# drivessop.net
KiCad netlist of a schematic drawn in EAGLE
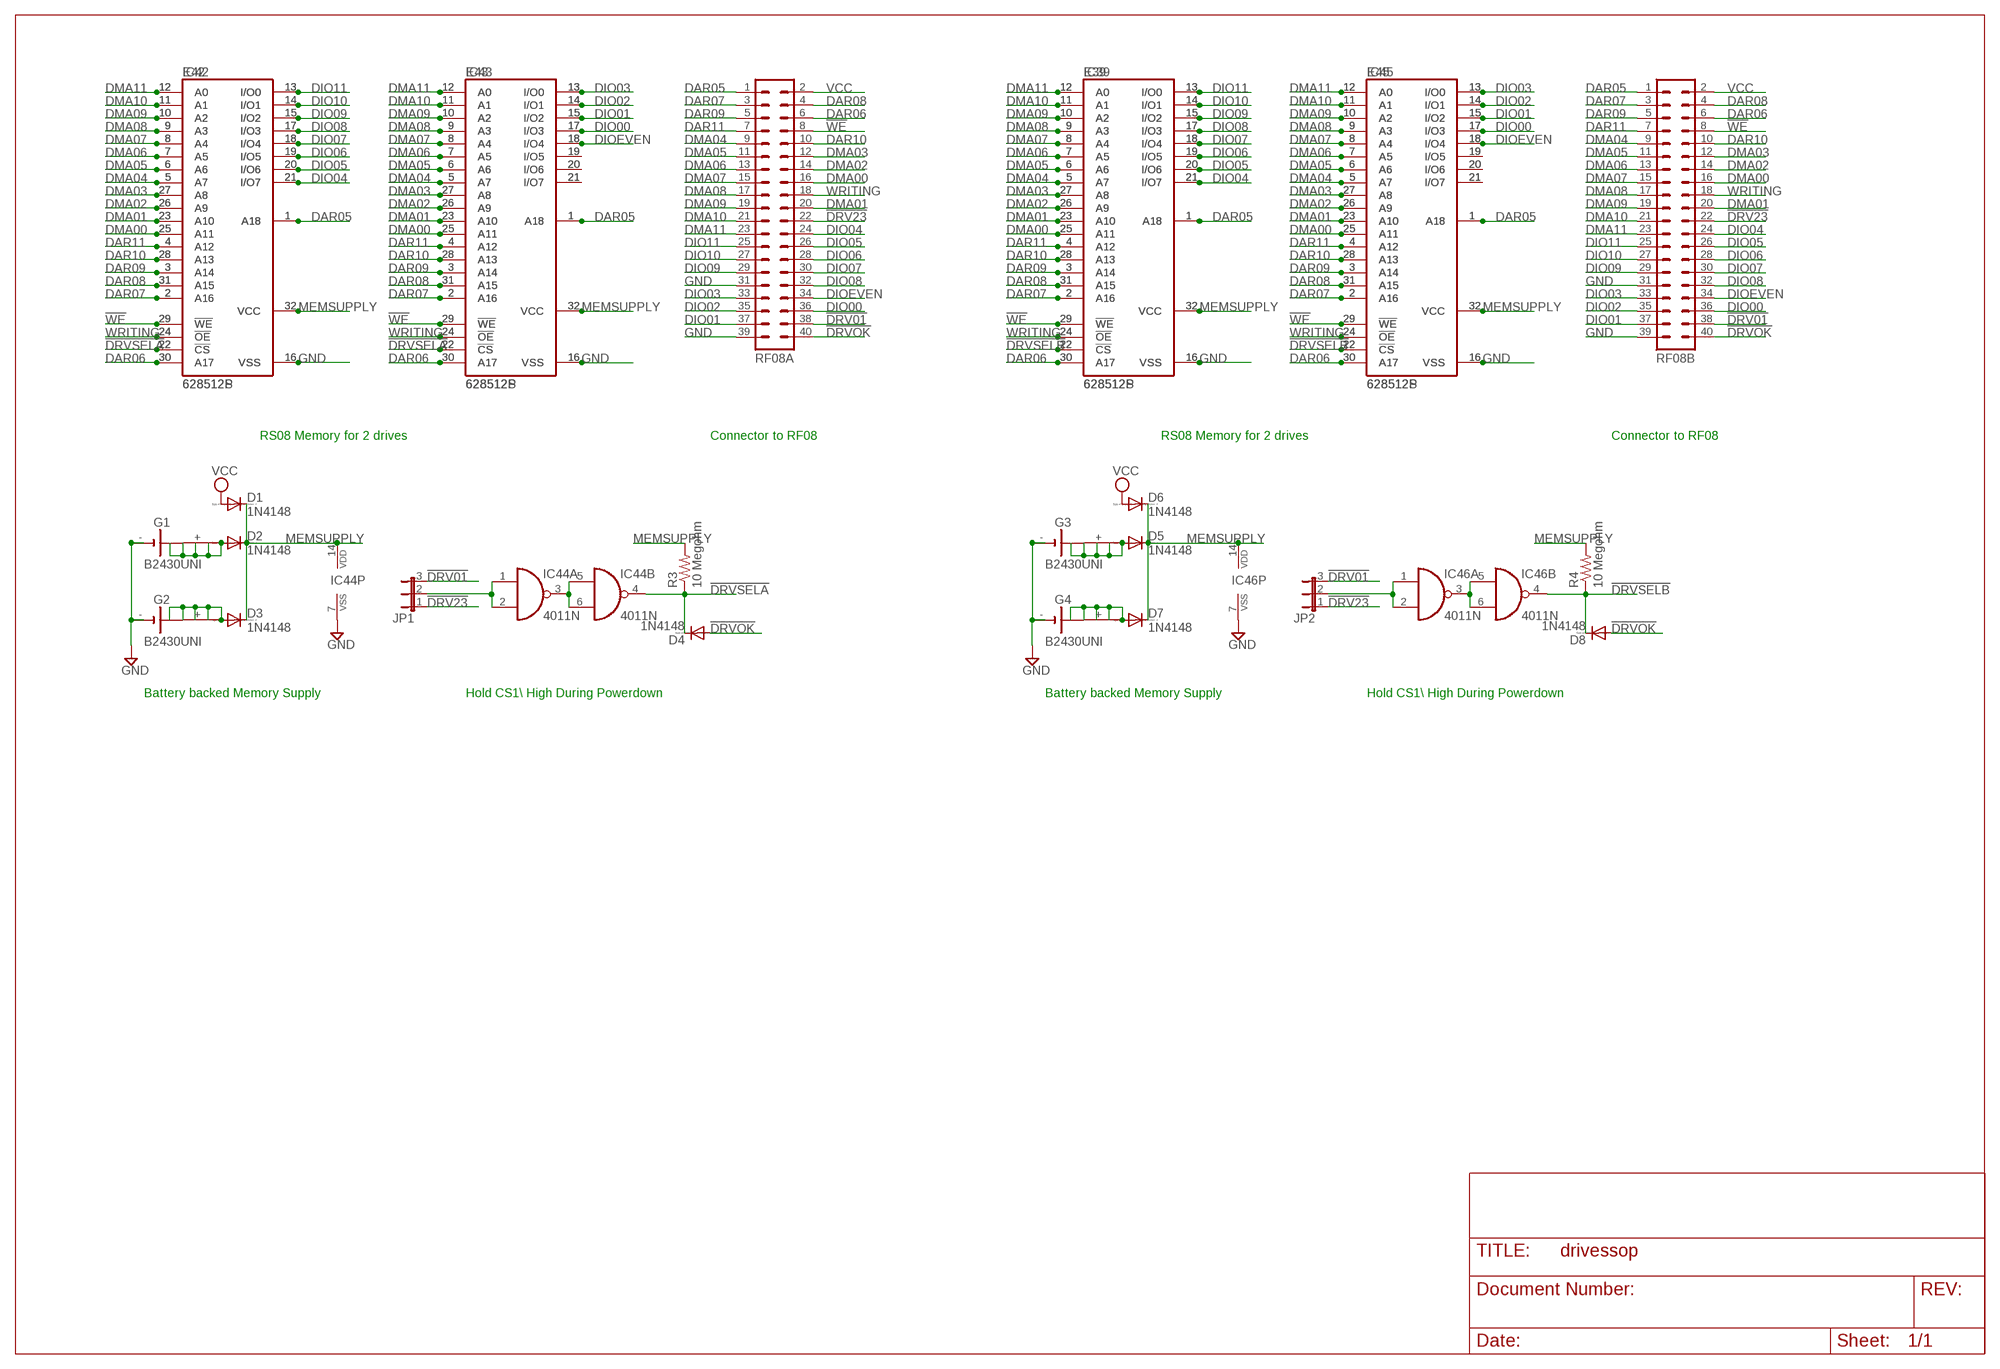
[diagram p0: schematic, sheet 1]

(export (version "E")
  (design (tool "Eeschema 10.0.6"))
  (components
    (comp (ref "D1")
      (value "1N4148")
      (footprint "eagle-import:DO35-10")
      (libsource (lib "eagle-import") (part "1N4148DO35-10"))
    )
    (comp (ref "D2")
      (value "1N4148")
      (footprint "eagle-import:DO35-10")
      (libsource (lib "eagle-import") (part "1N4148DO35-10"))
    )
    (comp (ref "D3")
      (value "1N4148")
      (footprint "eagle-import:DO35-10")
      (libsource (lib "eagle-import") (part "1N4148DO35-10"))
    )
    (comp (ref "D4")
      (value "1N4148")
      (footprint "eagle-import:DO35-10")
      (libsource (lib "eagle-import") (part "1N4148DO35-10"))
    )
    (comp (ref "D5")
      (value "1N4148")
      (footprint "eagle-import:DO35-10")
      (libsource (lib "eagle-import") (part "1N4148DO35-10"))
    )
    (comp (ref "D6")
      (value "1N4148")
      (footprint "eagle-import:DO35-10")
      (libsource (lib "eagle-import") (part "1N4148DO35-10"))
    )
    (comp (ref "D7")
      (value "1N4148")
      (footprint "eagle-import:DO35-10")
      (libsource (lib "eagle-import") (part "1N4148DO35-10"))
    )
    (comp (ref "D8")
      (value "1N4148")
      (footprint "eagle-import:DO35-10")
      (libsource (lib "eagle-import") (part "1N4148DO35-10"))
    )
    (comp (ref "E39")
      (value "628512S")
      (footprint "eagle-import:S032L")
      (libsource (lib "eagle-import") (part "628512S"))
    )
    (comp (ref "E42")
      (value "628512S")
      (footprint "eagle-import:S032L")
      (libsource (lib "eagle-import") (part "628512S"))
    )
    (comp (ref "E43")
      (value "628512S")
      (footprint "eagle-import:S032L")
      (libsource (lib "eagle-import") (part "628512S"))
    )
    (comp (ref "E45")
      (value "628512S")
      (footprint "eagle-import:S032L")
      (libsource (lib "eagle-import") (part "628512S"))
    )
    (comp (ref "G1")
      (value "B2430UNI")
      (footprint "eagle-import:B2430UNI")
      (libsource (lib "eagle-import") (part "B2430UNI"))
    )
    (comp (ref "G2")
      (value "B2430UNI")
      (footprint "eagle-import:B2430UNI")
      (libsource (lib "eagle-import") (part "B2430UNI"))
    )
    (comp (ref "G3")
      (value "B2430UNI")
      (footprint "eagle-import:B2430UNI")
      (libsource (lib "eagle-import") (part "B2430UNI"))
    )
    (comp (ref "G4")
      (value "B2430UNI")
      (footprint "eagle-import:B2430UNI")
      (libsource (lib "eagle-import") (part "B2430UNI"))
    )
    (comp (ref "IC39")
      (value "628512P")
      (footprint "eagle-import:DIL32")
      (libsource (lib "eagle-import") (part "628512P"))
    )
    (comp (ref "IC42")
      (value "628512P")
      (footprint "eagle-import:DIL32")
      (libsource (lib "eagle-import") (part "628512P"))
    )
    (comp (ref "IC43")
      (value "628512P")
      (footprint "eagle-import:DIL32")
      (libsource (lib "eagle-import") (part "628512P"))
    )
    (comp (ref "IC44")
      (value "4011N")
      (footprint "eagle-import:DIL14")
      (libsource (lib "eagle-import") (part "4011N"))
    )
    (comp (ref "IC45")
      (value "628512P")
      (footprint "eagle-import:DIL32")
      (libsource (lib "eagle-import") (part "628512P"))
    )
    (comp (ref "IC46")
      (value "4011N")
      (footprint "eagle-import:DIL14")
      (libsource (lib "eagle-import") (part "4011N"))
    )
    (comp (ref "JP1")
      (value "JP2E")
      (footprint "eagle-import:JP2")
      (libsource (lib "eagle-import") (part "JP2E"))
    )
    (comp (ref "JP2")
      (value "JP2E")
      (footprint "eagle-import:JP2")
      (libsource (lib "eagle-import") (part "JP2E"))
    )
    (comp (ref "R3")
      (value "10 Megohm")
      (footprint "eagle-import:0207_10")
      (libsource (lib "eagle-import") (part "R-US_0207/10"))
    )
    (comp (ref "R4")
      (value "10 Megohm")
      (footprint "eagle-import:0207_10")
      (libsource (lib "eagle-import") (part "R-US_0207/10"))
    )
    (comp (ref "RF08A")
      (value "MA20-2")
      (footprint "eagle-import:MA20-2")
      (libsource (lib "eagle-import") (part "MA20-2"))
    )
    (comp (ref "RF08B")
      (value "MA20-2")
      (footprint "eagle-import:MA20-2")
      (libsource (lib "eagle-import") (part "MA20-2"))
    )
  )
  (nets
    (net (code "1") (name "/DAR05") (class "Default")
      (node (ref "E39") (pin "1") (pinfunction "A18_1") (pintype "input"))
      (node (ref "E42") (pin "1") (pinfunction "A18_1") (pintype "input"))
      (node (ref "E43") (pin "1") (pinfunction "A18_1") (pintype "input"))
      (node (ref "E45") (pin "1") (pinfunction "A18_1") (pintype "input"))
      (node (ref "IC39") (pin "1") (pinfunction "A18_1") (pintype "input"))
      (node (ref "IC42") (pin "1") (pinfunction "A18_1") (pintype "input"))
      (node (ref "IC43") (pin "1") (pinfunction "A18_1") (pintype "input"))
      (node (ref "IC45") (pin "1") (pinfunction "A18_1") (pintype "input"))
      (node (ref "RF08A") (pin "1") (pinfunction "1_1") (pintype "passive"))
      (node (ref "RF08B") (pin "1") (pinfunction "1_1") (pintype "passive"))
    )
    (net (code "2") (name "/DAR06") (class "Default")
      (node (ref "E39") (pin "30") (pinfunction "A17_30") (pintype "input"))
      (node (ref "E42") (pin "30") (pinfunction "A17_30") (pintype "input"))
      (node (ref "E43") (pin "30") (pinfunction "A17_30") (pintype "input"))
      (node (ref "E45") (pin "30") (pinfunction "A17_30") (pintype "input"))
      (node (ref "IC39") (pin "30") (pinfunction "A17_30") (pintype "input"))
      (node (ref "IC42") (pin "30") (pinfunction "A17_30") (pintype "input"))
      (node (ref "IC43") (pin "30") (pinfunction "A17_30") (pintype "input"))
      (node (ref "IC45") (pin "30") (pinfunction "A17_30") (pintype "input"))
      (node (ref "RF08A") (pin "6") (pinfunction "6_6") (pintype "passive"))
      (node (ref "RF08B") (pin "6") (pinfunction "6_6") (pintype "passive"))
    )
    (net (code "3") (name "/DAR07") (class "Default")
      (node (ref "E39") (pin "2") (pinfunction "A16_2") (pintype "input"))
      (node (ref "E42") (pin "2") (pinfunction "A16_2") (pintype "input"))
      (node (ref "E43") (pin "2") (pinfunction "A16_2") (pintype "input"))
      (node (ref "E45") (pin "2") (pinfunction "A16_2") (pintype "input"))
      (node (ref "IC39") (pin "2") (pinfunction "A16_2") (pintype "input"))
      (node (ref "IC42") (pin "2") (pinfunction "A16_2") (pintype "input"))
      (node (ref "IC43") (pin "2") (pinfunction "A16_2") (pintype "input"))
      (node (ref "IC45") (pin "2") (pinfunction "A16_2") (pintype "input"))
      (node (ref "RF08A") (pin "3") (pinfunction "3_3") (pintype "passive"))
      (node (ref "RF08B") (pin "3") (pinfunction "3_3") (pintype "passive"))
    )
    (net (code "4") (name "/DAR08") (class "Default")
      (node (ref "E39") (pin "31") (pinfunction "A15_31") (pintype "input"))
      (node (ref "E42") (pin "31") (pinfunction "A15_31") (pintype "input"))
      (node (ref "E43") (pin "31") (pinfunction "A15_31") (pintype "input"))
      (node (ref "E45") (pin "31") (pinfunction "A15_31") (pintype "input"))
      (node (ref "IC39") (pin "31") (pinfunction "A15_31") (pintype "input"))
      (node (ref "IC42") (pin "31") (pinfunction "A15_31") (pintype "input"))
      (node (ref "IC43") (pin "31") (pinfunction "A15_31") (pintype "input"))
      (node (ref "IC45") (pin "31") (pinfunction "A15_31") (pintype "input"))
      (node (ref "RF08A") (pin "4") (pinfunction "4_4") (pintype "passive"))
      (node (ref "RF08B") (pin "4") (pinfunction "4_4") (pintype "passive"))
    )
    (net (code "5") (name "/DAR09") (class "Default")
      (node (ref "E39") (pin "3") (pinfunction "A14_3") (pintype "input"))
      (node (ref "E42") (pin "3") (pinfunction "A14_3") (pintype "input"))
      (node (ref "E43") (pin "3") (pinfunction "A14_3") (pintype "input"))
      (node (ref "E45") (pin "3") (pinfunction "A14_3") (pintype "input"))
      (node (ref "IC39") (pin "3") (pinfunction "A14_3") (pintype "input"))
      (node (ref "IC42") (pin "3") (pinfunction "A14_3") (pintype "input"))
      (node (ref "IC43") (pin "3") (pinfunction "A14_3") (pintype "input"))
      (node (ref "IC45") (pin "3") (pinfunction "A14_3") (pintype "input"))
      (node (ref "RF08A") (pin "5") (pinfunction "5_5") (pintype "passive"))
      (node (ref "RF08B") (pin "5") (pinfunction "5_5") (pintype "passive"))
    )
    (net (code "6") (name "/DAR10") (class "Default")
      (node (ref "E39") (pin "28") (pinfunction "A13_28") (pintype "input"))
      (node (ref "E42") (pin "28") (pinfunction "A13_28") (pintype "input"))
      (node (ref "E43") (pin "28") (pinfunction "A13_28") (pintype "input"))
      (node (ref "E45") (pin "28") (pinfunction "A13_28") (pintype "input"))
      (node (ref "IC39") (pin "28") (pinfunction "A13_28") (pintype "input"))
      (node (ref "IC42") (pin "28") (pinfunction "A13_28") (pintype "input"))
      (node (ref "IC43") (pin "28") (pinfunction "A13_28") (pintype "input"))
      (node (ref "IC45") (pin "28") (pinfunction "A13_28") (pintype "input"))
      (node (ref "RF08A") (pin "10") (pinfunction "10_10") (pintype "passive"))
      (node (ref "RF08B") (pin "10") (pinfunction "10_10") (pintype "passive"))
    )
    (net (code "7") (name "/DAR11") (class "Default")
      (node (ref "E39") (pin "4") (pinfunction "A12_4") (pintype "input"))
      (node (ref "E42") (pin "4") (pinfunction "A12_4") (pintype "input"))
      (node (ref "E43") (pin "4") (pinfunction "A12_4") (pintype "input"))
      (node (ref "E45") (pin "4") (pinfunction "A12_4") (pintype "input"))
      (node (ref "IC39") (pin "4") (pinfunction "A12_4") (pintype "input"))
      (node (ref "IC42") (pin "4") (pinfunction "A12_4") (pintype "input"))
      (node (ref "IC43") (pin "4") (pinfunction "A12_4") (pintype "input"))
      (node (ref "IC45") (pin "4") (pinfunction "A12_4") (pintype "input"))
      (node (ref "RF08A") (pin "7") (pinfunction "7_7") (pintype "passive"))
      (node (ref "RF08B") (pin "7") (pinfunction "7_7") (pintype "passive"))
    )
    (net (code "8") (name "/DIO00") (class "Default")
      (node (ref "E43") (pin "17") (pinfunction "I/O3_17") (pintype "bidirectional"))
      (node (ref "E45") (pin "17") (pinfunction "I/O3_17") (pintype "bidirectional"))
      (node (ref "IC43") (pin "17") (pinfunction "I/O3_17") (pintype "bidirectional"))
      (node (ref "IC45") (pin "17") (pinfunction "I/O3_17") (pintype "bidirectional"))
      (node (ref "RF08A") (pin "36") (pinfunction "36_36") (pintype "passive"))
      (node (ref "RF08B") (pin "36") (pinfunction "36_36") (pintype "passive"))
    )
    (net (code "9") (name "/DIO01") (class "Default")
      (node (ref "E43") (pin "15") (pinfunction "I/O2_15") (pintype "bidirectional"))
      (node (ref "E45") (pin "15") (pinfunction "I/O2_15") (pintype "bidirectional"))
      (node (ref "IC43") (pin "15") (pinfunction "I/O2_15") (pintype "bidirectional"))
      (node (ref "IC45") (pin "15") (pinfunction "I/O2_15") (pintype "bidirectional"))
      (node (ref "RF08A") (pin "37") (pinfunction "37_37") (pintype "passive"))
      (node (ref "RF08B") (pin "37") (pinfunction "37_37") (pintype "passive"))
    )
    (net (code "10") (name "/DIO02") (class "Default")
      (node (ref "E43") (pin "14") (pinfunction "I/O1_14") (pintype "bidirectional"))
      (node (ref "E45") (pin "14") (pinfunction "I/O1_14") (pintype "bidirectional"))
      (node (ref "IC43") (pin "14") (pinfunction "I/O1_14") (pintype "bidirectional"))
      (node (ref "IC45") (pin "14") (pinfunction "I/O1_14") (pintype "bidirectional"))
      (node (ref "RF08A") (pin "35") (pinfunction "35_35") (pintype "passive"))
      (node (ref "RF08B") (pin "35") (pinfunction "35_35") (pintype "passive"))
    )
    (net (code "11") (name "/DIO03") (class "Default")
      (node (ref "E43") (pin "13") (pinfunction "I/O0_13") (pintype "bidirectional"))
      (node (ref "E45") (pin "13") (pinfunction "I/O0_13") (pintype "bidirectional"))
      (node (ref "IC43") (pin "13") (pinfunction "I/O0_13") (pintype "bidirectional"))
      (node (ref "IC45") (pin "13") (pinfunction "I/O0_13") (pintype "bidirectional"))
      (node (ref "RF08A") (pin "33") (pinfunction "33_33") (pintype "passive"))
      (node (ref "RF08B") (pin "33") (pinfunction "33_33") (pintype "passive"))
    )
    (net (code "12") (name "/DIO04") (class "Default")
      (node (ref "E39") (pin "21") (pinfunction "I/O7_21") (pintype "bidirectional"))
      (node (ref "E42") (pin "21") (pinfunction "I/O7_21") (pintype "bidirectional"))
      (node (ref "IC39") (pin "21") (pinfunction "I/O7_21") (pintype "bidirectional"))
      (node (ref "IC42") (pin "21") (pinfunction "I/O7_21") (pintype "bidirectional"))
      (node (ref "RF08A") (pin "24") (pinfunction "24_24") (pintype "passive"))
      (node (ref "RF08B") (pin "24") (pinfunction "24_24") (pintype "passive"))
    )
    (net (code "13") (name "/DIO05") (class "Default")
      (node (ref "E39") (pin "20") (pinfunction "I/O6_20") (pintype "bidirectional"))
      (node (ref "E42") (pin "20") (pinfunction "I/O6_20") (pintype "bidirectional"))
      (node (ref "IC39") (pin "20") (pinfunction "I/O6_20") (pintype "bidirectional"))
      (node (ref "IC42") (pin "20") (pinfunction "I/O6_20") (pintype "bidirectional"))
      (node (ref "RF08A") (pin "26") (pinfunction "26_26") (pintype "passive"))
      (node (ref "RF08B") (pin "26") (pinfunction "26_26") (pintype "passive"))
    )
    (net (code "14") (name "/DIO06") (class "Default")
      (node (ref "E39") (pin "19") (pinfunction "I/O5_19") (pintype "bidirectional"))
      (node (ref "E42") (pin "19") (pinfunction "I/O5_19") (pintype "bidirectional"))
      (node (ref "IC39") (pin "19") (pinfunction "I/O5_19") (pintype "bidirectional"))
      (node (ref "IC42") (pin "19") (pinfunction "I/O5_19") (pintype "bidirectional"))
      (node (ref "RF08A") (pin "28") (pinfunction "28_28") (pintype "passive"))
      (node (ref "RF08B") (pin "28") (pinfunction "28_28") (pintype "passive"))
    )
    (net (code "15") (name "/DIO07") (class "Default")
      (node (ref "E39") (pin "18") (pinfunction "I/O4_18") (pintype "bidirectional"))
      (node (ref "E42") (pin "18") (pinfunction "I/O4_18") (pintype "bidirectional"))
      (node (ref "IC39") (pin "18") (pinfunction "I/O4_18") (pintype "bidirectional"))
      (node (ref "IC42") (pin "18") (pinfunction "I/O4_18") (pintype "bidirectional"))
      (node (ref "RF08A") (pin "30") (pinfunction "30_30") (pintype "passive"))
      (node (ref "RF08B") (pin "30") (pinfunction "30_30") (pintype "passive"))
    )
    (net (code "16") (name "/DIO08") (class "Default")
      (node (ref "E39") (pin "17") (pinfunction "I/O3_17") (pintype "bidirectional"))
      (node (ref "E42") (pin "17") (pinfunction "I/O3_17") (pintype "bidirectional"))
      (node (ref "IC39") (pin "17") (pinfunction "I/O3_17") (pintype "bidirectional"))
      (node (ref "IC42") (pin "17") (pinfunction "I/O3_17") (pintype "bidirectional"))
      (node (ref "RF08A") (pin "32") (pinfunction "32_32") (pintype "passive"))
      (node (ref "RF08B") (pin "32") (pinfunction "32_32") (pintype "passive"))
    )
    (net (code "17") (name "/DIO09") (class "Default")
      (node (ref "E39") (pin "15") (pinfunction "I/O2_15") (pintype "bidirectional"))
      (node (ref "E42") (pin "15") (pinfunction "I/O2_15") (pintype "bidirectional"))
      (node (ref "IC39") (pin "15") (pinfunction "I/O2_15") (pintype "bidirectional"))
      (node (ref "IC42") (pin "15") (pinfunction "I/O2_15") (pintype "bidirectional"))
      (node (ref "RF08A") (pin "29") (pinfunction "29_29") (pintype "passive"))
      (node (ref "RF08B") (pin "29") (pinfunction "29_29") (pintype "passive"))
    )
    (net (code "18") (name "/DIO10") (class "Default")
      (node (ref "E39") (pin "14") (pinfunction "I/O1_14") (pintype "bidirectional"))
      (node (ref "E42") (pin "14") (pinfunction "I/O1_14") (pintype "bidirectional"))
      (node (ref "IC39") (pin "14") (pinfunction "I/O1_14") (pintype "bidirectional"))
      (node (ref "IC42") (pin "14") (pinfunction "I/O1_14") (pintype "bidirectional"))
      (node (ref "RF08A") (pin "27") (pinfunction "27_27") (pintype "passive"))
      (node (ref "RF08B") (pin "27") (pinfunction "27_27") (pintype "passive"))
    )
    (net (code "19") (name "/DIO11") (class "Default")
      (node (ref "E39") (pin "13") (pinfunction "I/O0_13") (pintype "bidirectional"))
      (node (ref "E42") (pin "13") (pinfunction "I/O0_13") (pintype "bidirectional"))
      (node (ref "IC39") (pin "13") (pinfunction "I/O0_13") (pintype "bidirectional"))
      (node (ref "IC42") (pin "13") (pinfunction "I/O0_13") (pintype "bidirectional"))
      (node (ref "RF08A") (pin "25") (pinfunction "25_25") (pintype "passive"))
      (node (ref "RF08B") (pin "25") (pinfunction "25_25") (pintype "passive"))
    )
    (net (code "20") (name "/DIOEVEN") (class "Default")
      (node (ref "E43") (pin "18") (pinfunction "I/O4_18") (pintype "bidirectional"))
      (node (ref "E45") (pin "18") (pinfunction "I/O4_18") (pintype "bidirectional"))
      (node (ref "IC43") (pin "18") (pinfunction "I/O4_18") (pintype "bidirectional"))
      (node (ref "IC45") (pin "18") (pinfunction "I/O4_18") (pintype "bidirectional"))
      (node (ref "RF08A") (pin "34") (pinfunction "34_34") (pintype "passive"))
      (node (ref "RF08B") (pin "34") (pinfunction "34_34") (pintype "passive"))
    )
    (net (code "21") (name "/DMA00") (class "Default")
      (node (ref "E39") (pin "25") (pinfunction "A11_25") (pintype "input"))
      (node (ref "E42") (pin "25") (pinfunction "A11_25") (pintype "input"))
      (node (ref "E43") (pin "25") (pinfunction "A11_25") (pintype "input"))
      (node (ref "E45") (pin "25") (pinfunction "A11_25") (pintype "input"))
      (node (ref "IC39") (pin "25") (pinfunction "A11_25") (pintype "input"))
      (node (ref "IC42") (pin "25") (pinfunction "A11_25") (pintype "input"))
      (node (ref "IC43") (pin "25") (pinfunction "A11_25") (pintype "input"))
      (node (ref "IC45") (pin "25") (pinfunction "A11_25") (pintype "input"))
      (node (ref "RF08A") (pin "16") (pinfunction "16_16") (pintype "passive"))
      (node (ref "RF08B") (pin "16") (pinfunction "16_16") (pintype "passive"))
    )
    (net (code "22") (name "/DMA01") (class "Default")
      (node (ref "E39") (pin "23") (pinfunction "A10_23") (pintype "input"))
      (node (ref "E42") (pin "23") (pinfunction "A10_23") (pintype "input"))
      (node (ref "E43") (pin "23") (pinfunction "A10_23") (pintype "input"))
      (node (ref "E45") (pin "23") (pinfunction "A10_23") (pintype "input"))
      (node (ref "IC39") (pin "23") (pinfunction "A10_23") (pintype "input"))
      (node (ref "IC42") (pin "23") (pinfunction "A10_23") (pintype "input"))
      (node (ref "IC43") (pin "23") (pinfunction "A10_23") (pintype "input"))
      (node (ref "IC45") (pin "23") (pinfunction "A10_23") (pintype "input"))
      (node (ref "RF08A") (pin "20") (pinfunction "20_20") (pintype "passive"))
      (node (ref "RF08B") (pin "20") (pinfunction "20_20") (pintype "passive"))
    )
    (net (code "23") (name "/DMA02") (class "Default")
      (node (ref "E39") (pin "26") (pinfunction "A9_26") (pintype "input"))
      (node (ref "E42") (pin "26") (pinfunction "A9_26") (pintype "input"))
      (node (ref "E43") (pin "26") (pinfunction "A9_26") (pintype "input"))
      (node (ref "E45") (pin "26") (pinfunction "A9_26") (pintype "input"))
      (node (ref "IC39") (pin "26") (pinfunction "A9_26") (pintype "input"))
      (node (ref "IC42") (pin "26") (pinfunction "A9_26") (pintype "input"))
      (node (ref "IC43") (pin "26") (pinfunction "A9_26") (pintype "input"))
      (node (ref "IC45") (pin "26") (pinfunction "A9_26") (pintype "input"))
      (node (ref "RF08A") (pin "14") (pinfunction "14_14") (pintype "passive"))
      (node (ref "RF08B") (pin "14") (pinfunction "14_14") (pintype "passive"))
    )
    (net (code "24") (name "/DMA03") (class "Default")
      (node (ref "E39") (pin "27") (pinfunction "A8_27") (pintype "input"))
      (node (ref "E42") (pin "27") (pinfunction "A8_27") (pintype "input"))
      (node (ref "E43") (pin "27") (pinfunction "A8_27") (pintype "input"))
      (node (ref "E45") (pin "27") (pinfunction "A8_27") (pintype "input"))
      (node (ref "IC39") (pin "27") (pinfunction "A8_27") (pintype "input"))
      (node (ref "IC42") (pin "27") (pinfunction "A8_27") (pintype "input"))
      (node (ref "IC43") (pin "27") (pinfunction "A8_27") (pintype "input"))
      (node (ref "IC45") (pin "27") (pinfunction "A8_27") (pintype "input"))
      (node (ref "RF08A") (pin "12") (pinfunction "12_12") (pintype "passive"))
      (node (ref "RF08B") (pin "12") (pinfunction "12_12") (pintype "passive"))
    )
    (net (code "25") (name "/DMA04") (class "Default")
      (node (ref "E39") (pin "5") (pinfunction "A7_5") (pintype "input"))
      (node (ref "E42") (pin "5") (pinfunction "A7_5") (pintype "input"))
      (node (ref "E43") (pin "5") (pinfunction "A7_5") (pintype "input"))
      (node (ref "E45") (pin "5") (pinfunction "A7_5") (pintype "input"))
      (node (ref "IC39") (pin "5") (pinfunction "A7_5") (pintype "input"))
      (node (ref "IC42") (pin "5") (pinfunction "A7_5") (pintype "input"))
      (node (ref "IC43") (pin "5") (pinfunction "A7_5") (pintype "input"))
      (node (ref "IC45") (pin "5") (pinfunction "A7_5") (pintype "input"))
      (node (ref "RF08A") (pin "9") (pinfunction "9_9") (pintype "passive"))
      (node (ref "RF08B") (pin "9") (pinfunction "9_9") (pintype "passive"))
    )
    (net (code "26") (name "/DMA05") (class "Default")
      (node (ref "E39") (pin "6") (pinfunction "A6_6") (pintype "input"))
      (node (ref "E42") (pin "6") (pinfunction "A6_6") (pintype "input"))
      (node (ref "E43") (pin "6") (pinfunction "A6_6") (pintype "input"))
      (node (ref "E45") (pin "6") (pinfunction "A6_6") (pintype "input"))
      (node (ref "IC39") (pin "6") (pinfunction "A6_6") (pintype "input"))
      (node (ref "IC42") (pin "6") (pinfunction "A6_6") (pintype "input"))
      (node (ref "IC43") (pin "6") (pinfunction "A6_6") (pintype "input"))
      (node (ref "IC45") (pin "6") (pinfunction "A6_6") (pintype "input"))
      (node (ref "RF08A") (pin "11") (pinfunction "11_11") (pintype "passive"))
      (node (ref "RF08B") (pin "11") (pinfunction "11_11") (pintype "passive"))
    )
    (net (code "27") (name "/DMA06") (class "Default")
      (node (ref "E39") (pin "7") (pinfunction "A5_7") (pintype "input"))
      (node (ref "E42") (pin "7") (pinfunction "A5_7") (pintype "input"))
      (node (ref "E43") (pin "7") (pinfunction "A5_7") (pintype "input"))
      (node (ref "E45") (pin "7") (pinfunction "A5_7") (pintype "input"))
      (node (ref "IC39") (pin "7") (pinfunction "A5_7") (pintype "input"))
      (node (ref "IC42") (pin "7") (pinfunction "A5_7") (pintype "input"))
      (node (ref "IC43") (pin "7") (pinfunction "A5_7") (pintype "input"))
      (node (ref "IC45") (pin "7") (pinfunction "A5_7") (pintype "input"))
      (node (ref "RF08A") (pin "13") (pinfunction "13_13") (pintype "passive"))
      (node (ref "RF08B") (pin "13") (pinfunction "13_13") (pintype "passive"))
    )
    (net (code "28") (name "/DMA07") (class "Default")
      (node (ref "E39") (pin "8") (pinfunction "A4_8") (pintype "input"))
      (node (ref "E42") (pin "8") (pinfunction "A4_8") (pintype "input"))
      (node (ref "E43") (pin "8") (pinfunction "A4_8") (pintype "input"))
      (node (ref "E45") (pin "8") (pinfunction "A4_8") (pintype "input"))
      (node (ref "IC39") (pin "8") (pinfunction "A4_8") (pintype "input"))
      (node (ref "IC42") (pin "8") (pinfunction "A4_8") (pintype "input"))
      (node (ref "IC43") (pin "8") (pinfunction "A4_8") (pintype "input"))
      (node (ref "IC45") (pin "8") (pinfunction "A4_8") (pintype "input"))
      (node (ref "RF08A") (pin "15") (pinfunction "15_15") (pintype "passive"))
      (node (ref "RF08B") (pin "15") (pinfunction "15_15") (pintype "passive"))
    )
    (net (code "29") (name "/DMA08") (class "Default")
      (node (ref "E39") (pin "9") (pinfunction "A3_9") (pintype "input"))
      (node (ref "E42") (pin "9") (pinfunction "A3_9") (pintype "input"))
      (node (ref "E43") (pin "9") (pinfunction "A3_9") (pintype "input"))
      (node (ref "E45") (pin "9") (pinfunction "A3_9") (pintype "input"))
      (node (ref "IC39") (pin "9") (pinfunction "A3_9") (pintype "input"))
      (node (ref "IC42") (pin "9") (pinfunction "A3_9") (pintype "input"))
      (node (ref "IC43") (pin "9") (pinfunction "A3_9") (pintype "input"))
      (node (ref "IC45") (pin "9") (pinfunction "A3_9") (pintype "input"))
      (node (ref "RF08A") (pin "17") (pinfunction "17_17") (pintype "passive"))
      (node (ref "RF08B") (pin "17") (pinfunction "17_17") (pintype "passive"))
    )
    (net (code "30") (name "/DMA09") (class "Default")
      (node (ref "E39") (pin "10") (pinfunction "A2_10") (pintype "input"))
      (node (ref "E42") (pin "10") (pinfunction "A2_10") (pintype "input"))
      (node (ref "E43") (pin "10") (pinfunction "A2_10") (pintype "input"))
      (node (ref "E45") (pin "10") (pinfunction "A2_10") (pintype "input"))
      (node (ref "IC39") (pin "10") (pinfunction "A2_10") (pintype "input"))
      (node (ref "IC42") (pin "10") (pinfunction "A2_10") (pintype "input"))
      (node (ref "IC43") (pin "10") (pinfunction "A2_10") (pintype "input"))
      (node (ref "IC45") (pin "10") (pinfunction "A2_10") (pintype "input"))
      (node (ref "RF08A") (pin "19") (pinfunction "19_19") (pintype "passive"))
      (node (ref "RF08B") (pin "19") (pinfunction "19_19") (pintype "passive"))
    )
    (net (code "31") (name "/DMA10") (class "Default")
      (node (ref "E39") (pin "11") (pinfunction "A1_11") (pintype "input"))
      (node (ref "E42") (pin "11") (pinfunction "A1_11") (pintype "input"))
      (node (ref "E43") (pin "11") (pinfunction "A1_11") (pintype "input"))
      (node (ref "E45") (pin "11") (pinfunction "A1_11") (pintype "input"))
      (node (ref "IC39") (pin "11") (pinfunction "A1_11") (pintype "input"))
      (node (ref "IC42") (pin "11") (pinfunction "A1_11") (pintype "input"))
      (node (ref "IC43") (pin "11") (pinfunction "A1_11") (pintype "input"))
      (node (ref "IC45") (pin "11") (pinfunction "A1_11") (pintype "input"))
      (node (ref "RF08A") (pin "21") (pinfunction "21_21") (pintype "passive"))
      (node (ref "RF08B") (pin "21") (pinfunction "21_21") (pintype "passive"))
    )
    (net (code "32") (name "/DMA11") (class "Default")
      (node (ref "E39") (pin "12") (pinfunction "A0_12") (pintype "input"))
      (node (ref "E42") (pin "12") (pinfunction "A0_12") (pintype "input"))
      (node (ref "E43") (pin "12") (pinfunction "A0_12") (pintype "input"))
      (node (ref "E45") (pin "12") (pinfunction "A0_12") (pintype "input"))
      (node (ref "IC39") (pin "12") (pinfunction "A0_12") (pintype "input"))
      (node (ref "IC42") (pin "12") (pinfunction "A0_12") (pintype "input"))
      (node (ref "IC43") (pin "12") (pinfunction "A0_12") (pintype "input"))
      (node (ref "IC45") (pin "12") (pinfunction "A0_12") (pintype "input"))
      (node (ref "RF08A") (pin "23") (pinfunction "23_23") (pintype "passive"))
      (node (ref "RF08B") (pin "23") (pinfunction "23_23") (pintype "passive"))
    )
    (net (code "33") (name "/MEMSUPPLY") (class "Default")
      (node (ref "D1") (pin "C") (pinfunction "C_C") (pintype "passive"))
      (node (ref "D2") (pin "C") (pinfunction "C_C") (pintype "passive"))
      (node (ref "D3") (pin "C") (pinfunction "C_C") (pintype "passive"))
      (node (ref "D5") (pin "C") (pinfunction "C_C") (pintype "passive"))
      (node (ref "D6") (pin "C") (pinfunction "C_C") (pintype "passive"))
      (node (ref "D7") (pin "C") (pinfunction "C_C") (pintype "passive"))
      (node (ref "E39") (pin "32") (pinfunction "VCC_32") (pintype "power_in"))
      (node (ref "E42") (pin "32") (pinfunction "VCC_32") (pintype "power_in"))
      (node (ref "E43") (pin "32") (pinfunction "VCC_32") (pintype "power_in"))
      (node (ref "E45") (pin "32") (pinfunction "VCC_32") (pintype "power_in"))
      (node (ref "IC39") (pin "32") (pinfunction "VCC_32") (pintype "power_in"))
      (node (ref "IC42") (pin "32") (pinfunction "VCC_32") (pintype "power_in"))
      (node (ref "IC43") (pin "32") (pinfunction "VCC_32") (pintype "power_in"))
      (node (ref "IC44") (pin "14") (pinfunction "VDD_14") (pintype "power_in"))
      (node (ref "IC45") (pin "32") (pinfunction "VCC_32") (pintype "power_in"))
      (node (ref "IC46") (pin "14") (pinfunction "VDD_14") (pintype "power_in"))
      (node (ref "R3") (pin "2") (pinfunction "2_2") (pintype "passive"))
      (node (ref "R4") (pin "2") (pinfunction "2_2") (pintype "passive"))
    )
    (net (code "34") (name "/WRITING") (class "Default")
      (node (ref "E39") (pin "24") (pinfunction "~{OE}_24") (pintype "input"))
      (node (ref "E42") (pin "24") (pinfunction "~{OE}_24") (pintype "input"))
      (node (ref "E43") (pin "24") (pinfunction "~{OE}_24") (pintype "input"))
      (node (ref "E45") (pin "24") (pinfunction "~{OE}_24") (pintype "input"))
      (node (ref "IC39") (pin "24") (pinfunction "~{OE}_24") (pintype "input"))
      (node (ref "IC42") (pin "24") (pinfunction "~{OE}_24") (pintype "input"))
      (node (ref "IC43") (pin "24") (pinfunction "~{OE}_24") (pintype "input"))
      (node (ref "IC45") (pin "24") (pinfunction "~{OE}_24") (pintype "input"))
      (node (ref "RF08A") (pin "18") (pinfunction "18_18") (pintype "passive"))
      (node (ref "RF08B") (pin "18") (pinfunction "18_18") (pintype "passive"))
    )
    (net (code "35") (name "/~{DRV01}") (class "Default")
      (node (ref "JP1") (pin "3") (pinfunction "3_3") (pintype "passive"))
      (node (ref "JP2") (pin "3") (pinfunction "3_3") (pintype "passive"))
      (node (ref "RF08A") (pin "38") (pinfunction "38_38") (pintype "passive"))
      (node (ref "RF08B") (pin "38") (pinfunction "38_38") (pintype "passive"))
    )
    (net (code "36") (name "/~{DRV23}") (class "Default")
      (node (ref "JP1") (pin "1") (pinfunction "1_1") (pintype "passive"))
      (node (ref "JP2") (pin "1") (pinfunction "1_1") (pintype "passive"))
      (node (ref "RF08A") (pin "22") (pinfunction "22_22") (pintype "passive"))
      (node (ref "RF08B") (pin "22") (pinfunction "22_22") (pintype "passive"))
    )
    (net (code "37") (name "/~{DRVOK}") (class "Default")
      (node (ref "D4") (pin "A") (pinfunction "A_A") (pintype "passive"))
      (node (ref "D8") (pin "A") (pinfunction "A_A") (pintype "passive"))
      (node (ref "RF08A") (pin "40") (pinfunction "40_40") (pintype "passive"))
      (node (ref "RF08B") (pin "40") (pinfunction "40_40") (pintype "passive"))
    )
    (net (code "38") (name "/~{DRVSELA}") (class "Default")
      (node (ref "D4") (pin "C") (pinfunction "C_C") (pintype "passive"))
      (node (ref "E42") (pin "22") (pinfunction "~{CS}_22") (pintype "input"))
      (node (ref "E43") (pin "22") (pinfunction "~{CS}_22") (pintype "input"))
      (node (ref "IC42") (pin "22") (pinfunction "~{CS}_22") (pintype "input"))
      (node (ref "IC43") (pin "22") (pinfunction "~{CS}_22") (pintype "input"))
      (node (ref "IC44") (pin "4") (pinfunction "O_4") (pintype "output"))
      (node (ref "R3") (pin "1") (pinfunction "1_1") (pintype "passive"))
    )
    (net (code "39") (name "/~{DRVSELB}") (class "Default")
      (node (ref "D8") (pin "C") (pinfunction "C_C") (pintype "passive"))
      (node (ref "E39") (pin "22") (pinfunction "~{CS}_22") (pintype "input"))
      (node (ref "E45") (pin "22") (pinfunction "~{CS}_22") (pintype "input"))
      (node (ref "IC39") (pin "22") (pinfunction "~{CS}_22") (pintype "input"))
      (node (ref "IC45") (pin "22") (pinfunction "~{CS}_22") (pintype "input"))
      (node (ref "IC46") (pin "4") (pinfunction "O_4") (pintype "output"))
      (node (ref "R4") (pin "1") (pinfunction "1_1") (pintype "passive"))
    )
    (net (code "40") (name "/~{WE}") (class "Default")
      (node (ref "E39") (pin "29") (pinfunction "~{WE}_29") (pintype "input"))
      (node (ref "E42") (pin "29") (pinfunction "~{WE}_29") (pintype "input"))
      (node (ref "E43") (pin "29") (pinfunction "~{WE}_29") (pintype "input"))
      (node (ref "E45") (pin "29") (pinfunction "~{WE}_29") (pintype "input"))
      (node (ref "IC39") (pin "29") (pinfunction "~{WE}_29") (pintype "input"))
      (node (ref "IC42") (pin "29") (pinfunction "~{WE}_29") (pintype "input"))
      (node (ref "IC43") (pin "29") (pinfunction "~{WE}_29") (pintype "input"))
      (node (ref "IC45") (pin "29") (pinfunction "~{WE}_29") (pintype "input"))
      (node (ref "RF08A") (pin "8") (pinfunction "8_8") (pintype "passive"))
      (node (ref "RF08B") (pin "8") (pinfunction "8_8") (pintype "passive"))
    )
    (net (code "41") (name "GND") (class "Default")
      (node (ref "E39") (pin "16") (pinfunction "VSS_16") (pintype "power_in"))
      (node (ref "E42") (pin "16") (pinfunction "VSS_16") (pintype "power_in"))
      (node (ref "E43") (pin "16") (pinfunction "VSS_16") (pintype "power_in"))
      (node (ref "E45") (pin "16") (pinfunction "VSS_16") (pintype "power_in"))
      (node (ref "G1") (pin "-") (pinfunction "-_-") (pintype "passive"))
      (node (ref "G1") (pin "-@1") (pinfunction "-_-@1") (pintype "passive"))
      (node (ref "G2") (pin "-") (pinfunction "-_-") (pintype "passive"))
      (node (ref "G2") (pin "-@1") (pinfunction "-_-@1") (pintype "passive"))
      (node (ref "G3") (pin "-") (pinfunction "-_-") (pintype "passive"))
      (node (ref "G3") (pin "-@1") (pinfunction "-_-@1") (pintype "passive"))
      (node (ref "G4") (pin "-") (pinfunction "-_-") (pintype "passive"))
      (node (ref "G4") (pin "-@1") (pinfunction "-_-@1") (pintype "passive"))
      (node (ref "IC39") (pin "16") (pinfunction "VSS_16") (pintype "power_in"))
      (node (ref "IC42") (pin "16") (pinfunction "VSS_16") (pintype "power_in"))
      (node (ref "IC43") (pin "16") (pinfunction "VSS_16") (pintype "power_in"))
      (node (ref "IC44") (pin "7") (pinfunction "VSS_7") (pintype "power_in"))
      (node (ref "IC45") (pin "16") (pinfunction "VSS_16") (pintype "power_in"))
      (node (ref "IC46") (pin "7") (pinfunction "VSS_7") (pintype "power_in"))
      (node (ref "RF08A") (pin "31") (pinfunction "31_31") (pintype "passive"))
      (node (ref "RF08A") (pin "39") (pinfunction "39_39") (pintype "passive"))
      (node (ref "RF08B") (pin "31") (pinfunction "31_31") (pintype "passive"))
      (node (ref "RF08B") (pin "39") (pinfunction "39_39") (pintype "passive"))
    )
    (net (code "42") (name "Net-(D2-PadA)") (class "Default")
      (node (ref "D2") (pin "A") (pinfunction "A_A") (pintype "passive"))
      (node (ref "G1") (pin "+") (pinfunction "+_+") (pintype "passive"))
      (node (ref "G1") (pin "+@1") (pinfunction "+_+@1") (pintype "passive"))
      (node (ref "G1") (pin "+@2") (pinfunction "+_+@2") (pintype "passive"))
      (node (ref "G1") (pin "+@3") (pinfunction "+_+@3") (pintype "passive"))
      (node (ref "G1") (pin "+@4") (pinfunction "+_+@4") (pintype "passive"))
    )
    (net (code "43") (name "Net-(D3-PadA)") (class "Default")
      (node (ref "D3") (pin "A") (pinfunction "A_A") (pintype "passive"))
      (node (ref "G2") (pin "+") (pinfunction "+_+") (pintype "passive"))
      (node (ref "G2") (pin "+@1") (pinfunction "+_+@1") (pintype "passive"))
      (node (ref "G2") (pin "+@2") (pinfunction "+_+@2") (pintype "passive"))
      (node (ref "G2") (pin "+@3") (pinfunction "+_+@3") (pintype "passive"))
      (node (ref "G2") (pin "+@4") (pinfunction "+_+@4") (pintype "passive"))
    )
    (net (code "44") (name "Net-(D5-PadA)") (class "Default")
      (node (ref "D5") (pin "A") (pinfunction "A_A") (pintype "passive"))
      (node (ref "G3") (pin "+") (pinfunction "+_+") (pintype "passive"))
      (node (ref "G3") (pin "+@1") (pinfunction "+_+@1") (pintype "passive"))
      (node (ref "G3") (pin "+@2") (pinfunction "+_+@2") (pintype "passive"))
      (node (ref "G3") (pin "+@3") (pinfunction "+_+@3") (pintype "passive"))
      (node (ref "G3") (pin "+@4") (pinfunction "+_+@4") (pintype "passive"))
    )
    (net (code "45") (name "Net-(D7-PadA)") (class "Default")
      (node (ref "D7") (pin "A") (pinfunction "A_A") (pintype "passive"))
      (node (ref "G4") (pin "+") (pinfunction "+_+") (pintype "passive"))
      (node (ref "G4") (pin "+@1") (pinfunction "+_+@1") (pintype "passive"))
      (node (ref "G4") (pin "+@2") (pinfunction "+_+@2") (pintype "passive"))
      (node (ref "G4") (pin "+@3") (pinfunction "+_+@3") (pintype "passive"))
      (node (ref "G4") (pin "+@4") (pinfunction "+_+@4") (pintype "passive"))
    )
    (net (code "46") (name "Net-(E43-I{slash}O5)") (class "Default")
      (node (ref "E43") (pin "19") (pinfunction "I/O5_19") (pintype "bidirectional"))
      (node (ref "IC43") (pin "19") (pinfunction "I/O5_19") (pintype "bidirectional"))
    )
    (net (code "47") (name "Net-(E43-I{slash}O6)") (class "Default")
      (node (ref "E43") (pin "20") (pinfunction "I/O6_20") (pintype "bidirectional"))
      (node (ref "IC43") (pin "20") (pinfunction "I/O6_20") (pintype "bidirectional"))
    )
    (net (code "48") (name "Net-(E43-I{slash}O7)") (class "Default")
      (node (ref "E43") (pin "21") (pinfunction "I/O7_21") (pintype "bidirectional"))
      (node (ref "IC43") (pin "21") (pinfunction "I/O7_21") (pintype "bidirectional"))
    )
    (net (code "49") (name "Net-(E45-I{slash}O5)") (class "Default")
      (node (ref "E45") (pin "19") (pinfunction "I/O5_19") (pintype "bidirectional"))
      (node (ref "IC45") (pin "19") (pinfunction "I/O5_19") (pintype "bidirectional"))
    )
    (net (code "50") (name "Net-(E45-I{slash}O6)") (class "Default")
      (node (ref "E45") (pin "20") (pinfunction "I/O6_20") (pintype "bidirectional"))
      (node (ref "IC45") (pin "20") (pinfunction "I/O6_20") (pintype "bidirectional"))
    )
    (net (code "51") (name "Net-(E45-I{slash}O7)") (class "Default")
      (node (ref "E45") (pin "21") (pinfunction "I/O7_21") (pintype "bidirectional"))
      (node (ref "IC45") (pin "21") (pinfunction "I/O7_21") (pintype "bidirectional"))
    )
    (net (code "52") (name "Net-(IC44A-I0)") (class "Default")
      (node (ref "IC44") (pin "1") (pinfunction "I0_1") (pintype "input"))
      (node (ref "IC44") (pin "2") (pinfunction "I1_2") (pintype "input"))
      (node (ref "JP1") (pin "2") (pinfunction "2_2") (pintype "passive"))
    )
    (net (code "53") (name "Net-(IC44A-O)") (class "Default")
      (node (ref "IC44") (pin "3") (pinfunction "O_3") (pintype "output"))
      (node (ref "IC44") (pin "5") (pinfunction "I0_5") (pintype "input"))
      (node (ref "IC44") (pin "6") (pinfunction "I1_6") (pintype "input"))
    )
    (net (code "54") (name "Net-(IC46A-I0)") (class "Default")
      (node (ref "IC46") (pin "1") (pinfunction "I0_1") (pintype "input"))
      (node (ref "IC46") (pin "2") (pinfunction "I1_2") (pintype "input"))
      (node (ref "JP2") (pin "2") (pinfunction "2_2") (pintype "passive"))
    )
    (net (code "55") (name "Net-(IC46A-O)") (class "Default")
      (node (ref "IC46") (pin "3") (pinfunction "O_3") (pintype "output"))
      (node (ref "IC46") (pin "5") (pinfunction "I0_5") (pintype "input"))
      (node (ref "IC46") (pin "6") (pinfunction "I1_6") (pintype "input"))
    )
    (net (code "56") (name "VCC") (class "Default")
      (node (ref "D1") (pin "A") (pinfunction "A_A") (pintype "passive"))
      (node (ref "D6") (pin "A") (pinfunction "A_A") (pintype "passive"))
      (node (ref "RF08A") (pin "2") (pinfunction "2_2") (pintype "passive"))
      (node (ref "RF08B") (pin "2") (pinfunction "2_2") (pintype "passive"))
    )
  )
)
